# lm317-laser-driver-mk-1_0.net
KiCad netlist of a schematic drawn in EAGLE
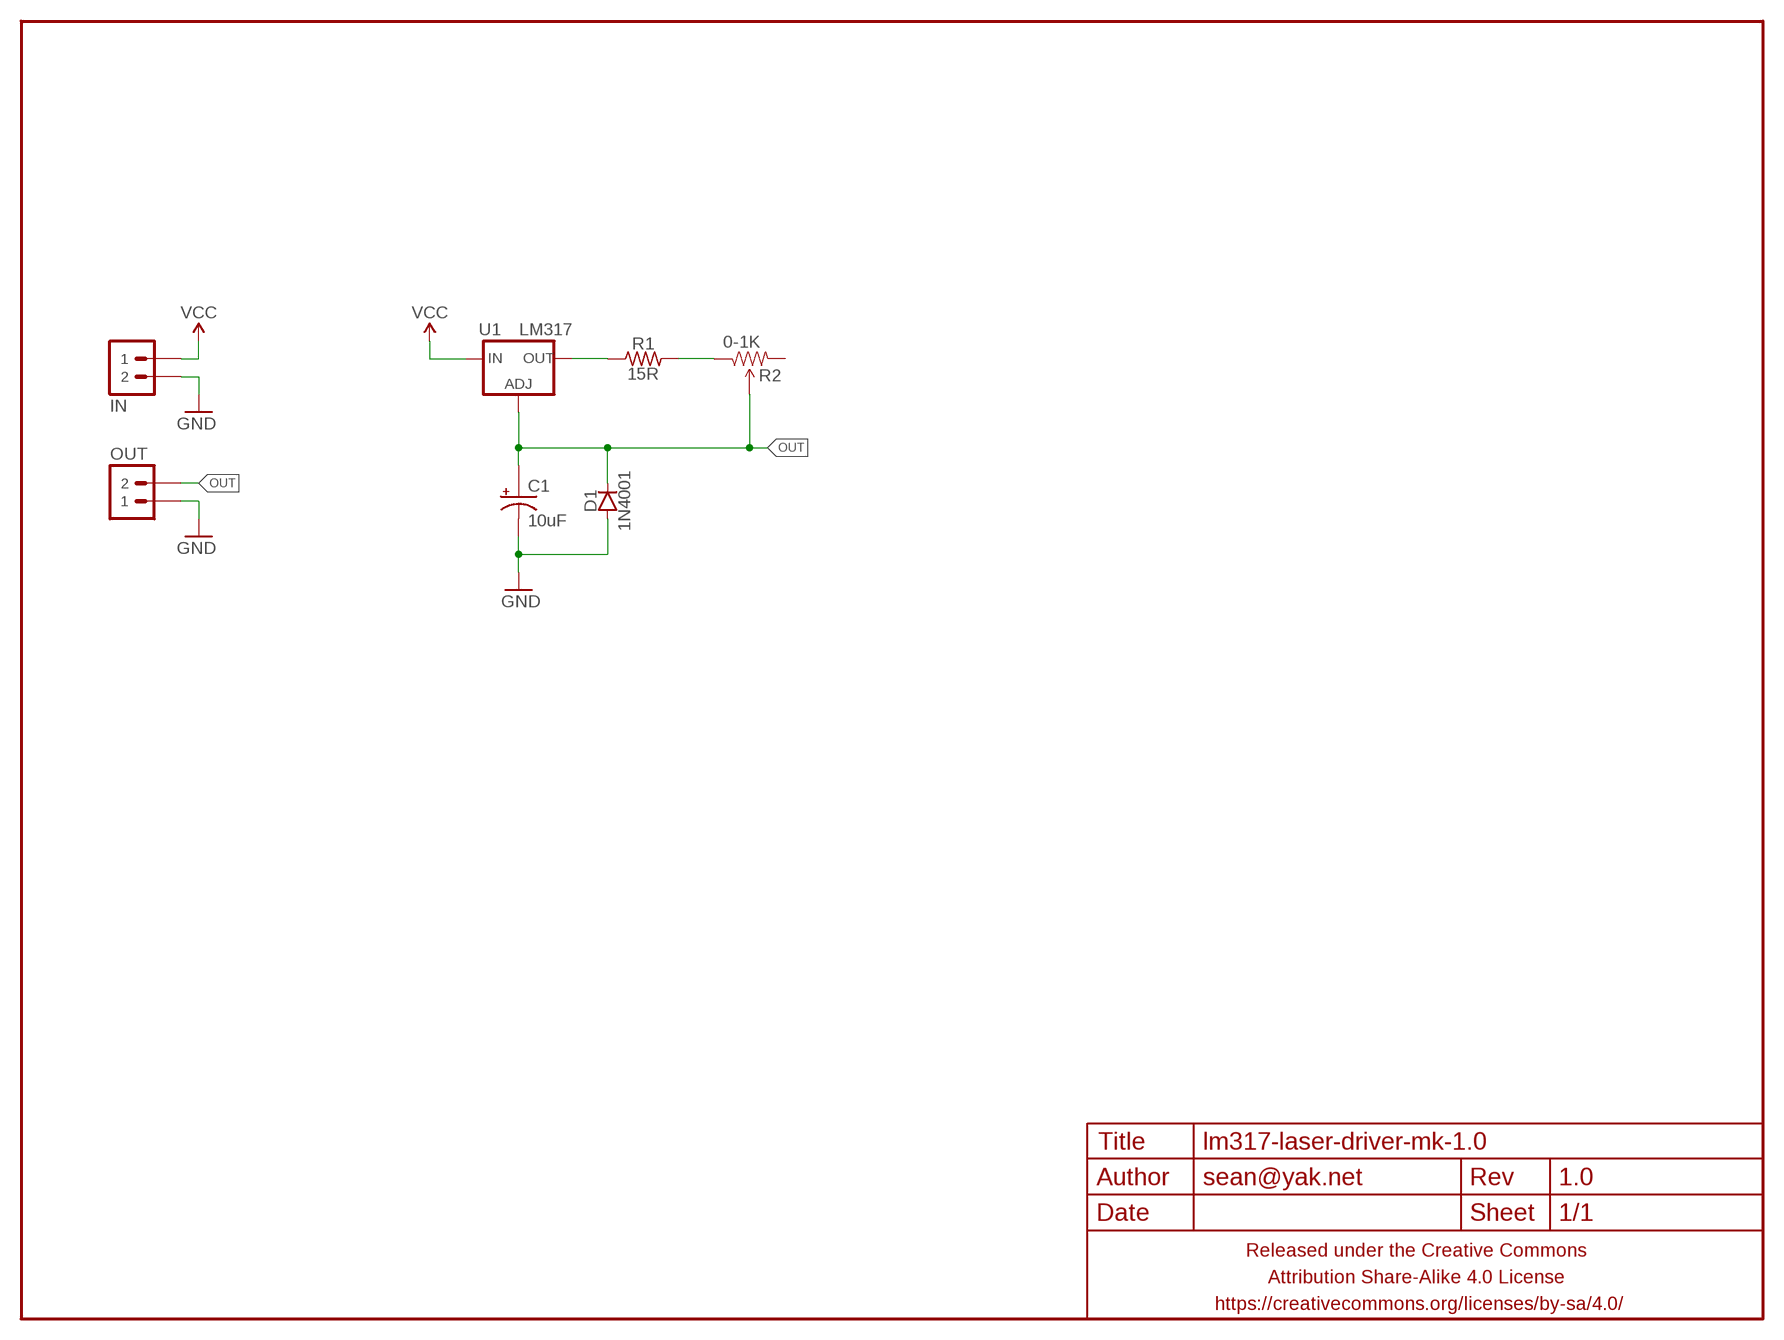
[diagram p0: schematic, sheet 1]

(export (version "E")
  (design (tool "Eeschema 10.0.6"))
  (components
    (comp (ref "C1")
      (value "10uF")
      (footprint "eagle-import:E2,5-6")
      (libsource (lib "eagle-import") (part "CAPACITOR-POLARIZEDE2.5-6"))
    )
    (comp (ref "D1")
      (value "1N4001")
      (footprint "eagle-import:DIODE-10.16MM-NOSYMBOL")
      (libsource (lib "eagle-import") (part "DIODEPTH-10.68MM-NOSYM"))
    )
    (comp (ref "FRAME1")
      (value "FRAME-LETTERNO_PACKAGE")
      (footprint "eagle-import:DUMMY")
      (fields (field (name "DESIGNER") "sean@yak.net") (field (name "VERSION") "1.0"))
      (libsource (lib "eagle-import") (part "FRAME-LETTERNO_PACKAGE"))
    )
    (comp (ref "IN")
      (value "M02PTH-CENTERED-R+")
      (footprint "eagle-import:1X02-CENTER-R+")
      (libsource (lib "eagle-import") (part "M02PTH-CENTERED-R+"))
    )
    (comp (ref "OUT")
      (value "M02PTH-CENTERED-R+")
      (footprint "eagle-import:1X02-CENTER-R+")
      (libsource (lib "eagle-import") (part "M02PTH-CENTERED-R+"))
    )
    (comp (ref "R1")
      (value "15R")
      (footprint "eagle-import:RESISTOR-AXIAL-PTH-10.16MM")
      (libsource (lib "eagle-import") (part "RESISTORPTH-AXIAL-10.16MM"))
    )
    (comp (ref "R2")
      (value "0-1K")
      (footprint "eagle-import:TRIM_POT_PTH2")
      (libsource (lib "eagle-import") (part "TRIMPOTPTH2"))
    )
    (comp (ref "U1")
      (value "LM317")
      (footprint "eagle-import:TO220-THERMPAD")
      (libsource (lib "eagle-import") (part "V_REG_317THERMPAD"))
    )
  )
  (nets
    (net (code "1") (name "GND") (class "Default")
      (node (ref "C1") (pin "-") (pinfunction "-_-") (pintype "passive"))
      (node (ref "D1") (pin "A") (pinfunction "A_A") (pintype "passive"))
      (node (ref "IN") (pin "2") (pinfunction "2_2") (pintype "passive"))
      (node (ref "OUT") (pin "1") (pinfunction "1_1") (pintype "passive"))
    )
    (net (code "2") (name "Net-(R1-1)") (class "Default")
      (node (ref "R1") (pin "P$1") (pinfunction "1_P$1") (pintype "passive"))
      (node (ref "U1") (pin "2@1") (pinfunction "OUT_2@1") (pintype "output"))
      (node (ref "U1") (pin "2@2") (pinfunction "OUT_2@2") (pintype "output"))
    )
    (net (code "3") (name "Net-(R1-2)") (class "Default")
      (node (ref "R1") (pin "P$2") (pinfunction "2_P$2") (pintype "passive"))
      (node (ref "R2") (pin "1") (pinfunction "CCW_1") (pintype "passive"))
    )
    (net (code "4") (name "OUT") (class "Default")
      (node (ref "C1") (pin "+") (pinfunction "+_+") (pintype "passive"))
      (node (ref "D1") (pin "C") (pinfunction "C_C") (pintype "passive"))
      (node (ref "OUT") (pin "2") (pinfunction "2_2") (pintype "passive"))
      (node (ref "R2") (pin "2") (pinfunction "WIPER_2") (pintype "passive"))
      (node (ref "U1") (pin "1") (pinfunction "ADJ_1") (pintype "input"))
    )
    (net (code "5") (name "VCC") (class "Default")
      (node (ref "IN") (pin "1") (pinfunction "1_1") (pintype "passive"))
      (node (ref "U1") (pin "3") (pinfunction "IN_3") (pintype "input"))
    )
    (net (code "6") (name "unconnected-(R2-CW-Pad3)") (class "Default")
      (node (ref "R2") (pin "3") (pinfunction "CW_3") (pintype "passive"))
    )
  )
)
